# MS5607.net
KiCad netlist of a schematic drawn in Altium Designer
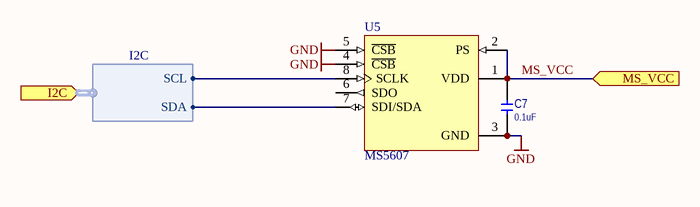
[diagram p0: MS5607.SchDoc]

(export (version "E")
  (design (tool "Eeschema 10.0.6"))
  (components
    (comp (ref "C7")
      (value "0.1uF")
      (footprint "CERCAP 0402")
      (description "Capacitor")
      (fields (field (name "Comment") "CERCAP 0402 0.1uF * X7R"))
      (libsource (lib "!main") (part "!Capacitor"))
    )
    (comp (ref "U5")
      (value "MS5607")
      (footprint "QFN-8(MS5607)")
      (description "Temp/Pres")
      (libsource (lib "sensors") (part "MS5607"))
    )
  )
  (nets
    (net (code "2") (name "/MS_VCC") (class "Default")
      (node (ref "C7") (pin "2") (pintype "passive"))
      (node (ref "U5") (pin "1") (pinfunction "VDD_1") (pintype "power_in"))
      (node (ref "U5") (pin "2") (pinfunction "PS_2") (pintype "input"))
    )
    (net (code "3") (name "/SCL") (class "Default")
      (node (ref "U5") (pin "8") (pinfunction "SCLK_8") (pintype "input"))
    )
    (net (code "4") (name "/SDA") (class "Default")
      (node (ref "U5") (pin "7") (pinfunction "SDI/SDA_7") (pintype "bidirectional"))
    )
    (net (code "6") (name "GND") (class "Default")
      (node (ref "C7") (pin "1") (pintype "passive"))
      (node (ref "U5") (pin "3") (pinfunction "GND_3") (pintype "power_in"))
      (node (ref "U5") (pin "4") (pinfunction "~{CSB}_4") (pintype "input"))
      (node (ref "U5") (pin "5") (pinfunction "~{CSB}_5") (pintype "input"))
    )
    (net (code "7") (name "unconnected-(U5-SDO-Pad6)") (class "Default")
      (node (ref "U5") (pin "6") (pinfunction "SDO_6") (pintype "output"))
    )
  )
)
